# PRY417_Med.net
KiCad netlist of a schematic drawn in EAGLE
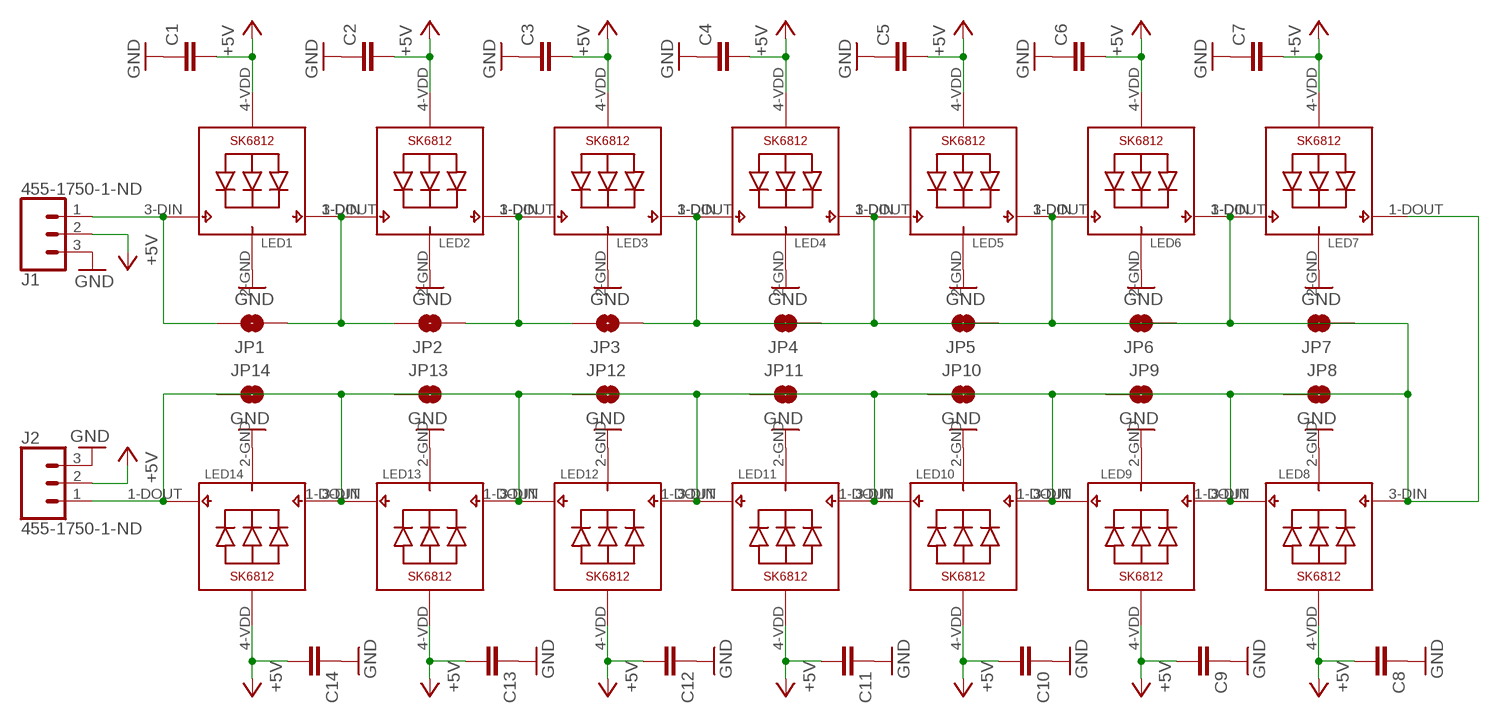
[diagram p0: schematic, sheet 1]

(export (version "E")
  (design (tool "Eeschema 10.0.6"))
  (components
    (comp (ref "C1")
      (value "C-EUC1206")
      (footprint "eagle-import:C1206")
      (libsource (lib "eagle-import") (part "C-EUC1206"))
    )
    (comp (ref "C2")
      (value "C-EUC1206")
      (footprint "eagle-import:C1206")
      (libsource (lib "eagle-import") (part "C-EUC1206"))
    )
    (comp (ref "C3")
      (value "C-EUC1206")
      (footprint "eagle-import:C1206")
      (libsource (lib "eagle-import") (part "C-EUC1206"))
    )
    (comp (ref "C4")
      (value "C-EUC1206")
      (footprint "eagle-import:C1206")
      (libsource (lib "eagle-import") (part "C-EUC1206"))
    )
    (comp (ref "C5")
      (value "C-EUC1206")
      (footprint "eagle-import:C1206")
      (libsource (lib "eagle-import") (part "C-EUC1206"))
    )
    (comp (ref "C6")
      (value "C-EUC1206")
      (footprint "eagle-import:C1206")
      (libsource (lib "eagle-import") (part "C-EUC1206"))
    )
    (comp (ref "C7")
      (value "C-EUC1206")
      (footprint "eagle-import:C1206")
      (libsource (lib "eagle-import") (part "C-EUC1206"))
    )
    (comp (ref "C8")
      (value "C-EUC1206")
      (footprint "eagle-import:C1206")
      (libsource (lib "eagle-import") (part "C-EUC1206"))
    )
    (comp (ref "C9")
      (value "C-EUC1206")
      (footprint "eagle-import:C1206")
      (libsource (lib "eagle-import") (part "C-EUC1206"))
    )
    (comp (ref "C10")
      (value "C-EUC1206")
      (footprint "eagle-import:C1206")
      (libsource (lib "eagle-import") (part "C-EUC1206"))
    )
    (comp (ref "C11")
      (value "C-EUC1206")
      (footprint "eagle-import:C1206")
      (libsource (lib "eagle-import") (part "C-EUC1206"))
    )
    (comp (ref "C12")
      (value "C-EUC1206")
      (footprint "eagle-import:C1206")
      (libsource (lib "eagle-import") (part "C-EUC1206"))
    )
    (comp (ref "C13")
      (value "C-EUC1206")
      (footprint "eagle-import:C1206")
      (libsource (lib "eagle-import") (part "C-EUC1206"))
    )
    (comp (ref "C14")
      (value "C-EUC1206")
      (footprint "eagle-import:C1206")
      (libsource (lib "eagle-import") (part "C-EUC1206"))
    )
    (comp (ref "J1")
      (value "455-1750-1-ND")
      (footprint "eagle-import:1X03")
      (libsource (lib "eagle-import") (part "CONN_03"))
    )
    (comp (ref "J2")
      (value "455-1750-1-ND")
      (footprint "eagle-import:1X03")
      (libsource (lib "eagle-import") (part "CONN_03"))
    )
    (comp (ref "JP1")
      (value "JUMPER-SMT_2_NO_SILK")
      (footprint "eagle-import:SMT-JUMPER_2_NO_SILK")
      (libsource (lib "eagle-import") (part "JUMPER-SMT_2_NO_SILK"))
    )
    (comp (ref "JP2")
      (value "JUMPER-SMT_2_NO_SILK")
      (footprint "eagle-import:SMT-JUMPER_2_NO_SILK")
      (libsource (lib "eagle-import") (part "JUMPER-SMT_2_NO_SILK"))
    )
    (comp (ref "JP3")
      (value "JUMPER-SMT_2_NO_SILK")
      (footprint "eagle-import:SMT-JUMPER_2_NO_SILK")
      (libsource (lib "eagle-import") (part "JUMPER-SMT_2_NO_SILK"))
    )
    (comp (ref "JP4")
      (value "JUMPER-SMT_2_NO_SILK")
      (footprint "eagle-import:SMT-JUMPER_2_NO_SILK")
      (libsource (lib "eagle-import") (part "JUMPER-SMT_2_NO_SILK"))
    )
    (comp (ref "JP5")
      (value "JUMPER-SMT_2_NO_SILK")
      (footprint "eagle-import:SMT-JUMPER_2_NO_SILK")
      (libsource (lib "eagle-import") (part "JUMPER-SMT_2_NO_SILK"))
    )
    (comp (ref "JP6")
      (value "JUMPER-SMT_2_NO_SILK")
      (footprint "eagle-import:SMT-JUMPER_2_NO_SILK")
      (libsource (lib "eagle-import") (part "JUMPER-SMT_2_NO_SILK"))
    )
    (comp (ref "JP7")
      (value "JUMPER-SMT_2_NO_SILK")
      (footprint "eagle-import:SMT-JUMPER_2_NO_SILK")
      (libsource (lib "eagle-import") (part "JUMPER-SMT_2_NO_SILK"))
    )
    (comp (ref "JP8")
      (value "JUMPER-SMT_2_NO_SILK")
      (footprint "eagle-import:SMT-JUMPER_2_NO_SILK")
      (libsource (lib "eagle-import") (part "JUMPER-SMT_2_NO_SILK"))
    )
    (comp (ref "JP9")
      (value "JUMPER-SMT_2_NO_SILK")
      (footprint "eagle-import:SMT-JUMPER_2_NO_SILK")
      (libsource (lib "eagle-import") (part "JUMPER-SMT_2_NO_SILK"))
    )
    (comp (ref "JP10")
      (value "JUMPER-SMT_2_NO_SILK")
      (footprint "eagle-import:SMT-JUMPER_2_NO_SILK")
      (libsource (lib "eagle-import") (part "JUMPER-SMT_2_NO_SILK"))
    )
    (comp (ref "JP11")
      (value "JUMPER-SMT_2_NO_SILK")
      (footprint "eagle-import:SMT-JUMPER_2_NO_SILK")
      (libsource (lib "eagle-import") (part "JUMPER-SMT_2_NO_SILK"))
    )
    (comp (ref "JP12")
      (value "JUMPER-SMT_2_NO_SILK")
      (footprint "eagle-import:SMT-JUMPER_2_NO_SILK")
      (libsource (lib "eagle-import") (part "JUMPER-SMT_2_NO_SILK"))
    )
    (comp (ref "JP13")
      (value "JUMPER-SMT_2_NO_SILK")
      (footprint "eagle-import:SMT-JUMPER_2_NO_SILK")
      (libsource (lib "eagle-import") (part "JUMPER-SMT_2_NO_SILK"))
    )
    (comp (ref "JP14")
      (value "JUMPER-SMT_2_NO_SILK")
      (footprint "eagle-import:SMT-JUMPER_2_NO_SILK")
      (libsource (lib "eagle-import") (part "JUMPER-SMT_2_NO_SILK"))
    )
    (comp (ref "LED1")
      (value "SK6812_3535")
      (footprint "eagle-import:LED3535")
      (libsource (lib "eagle-import") (part "SK6812_3535"))
    )
    (comp (ref "LED2")
      (value "SK6812_3535")
      (footprint "eagle-import:LED3535")
      (libsource (lib "eagle-import") (part "SK6812_3535"))
    )
    (comp (ref "LED3")
      (value "SK6812_3535")
      (footprint "eagle-import:LED3535")
      (libsource (lib "eagle-import") (part "SK6812_3535"))
    )
    (comp (ref "LED4")
      (value "SK6812_3535")
      (footprint "eagle-import:LED3535")
      (libsource (lib "eagle-import") (part "SK6812_3535"))
    )
    (comp (ref "LED5")
      (value "SK6812_3535")
      (footprint "eagle-import:LED3535")
      (libsource (lib "eagle-import") (part "SK6812_3535"))
    )
    (comp (ref "LED6")
      (value "SK6812_3535")
      (footprint "eagle-import:LED3535")
      (libsource (lib "eagle-import") (part "SK6812_3535"))
    )
    (comp (ref "LED7")
      (value "SK6812_3535")
      (footprint "eagle-import:LED3535")
      (libsource (lib "eagle-import") (part "SK6812_3535"))
    )
    (comp (ref "LED8")
      (value "SK6812_3535")
      (footprint "eagle-import:LED3535")
      (libsource (lib "eagle-import") (part "SK6812_3535"))
    )
    (comp (ref "LED9")
      (value "SK6812_3535")
      (footprint "eagle-import:LED3535")
      (libsource (lib "eagle-import") (part "SK6812_3535"))
    )
    (comp (ref "LED10")
      (value "SK6812_3535")
      (footprint "eagle-import:LED3535")
      (libsource (lib "eagle-import") (part "SK6812_3535"))
    )
    (comp (ref "LED11")
      (value "SK6812_3535")
      (footprint "eagle-import:LED3535")
      (libsource (lib "eagle-import") (part "SK6812_3535"))
    )
    (comp (ref "LED12")
      (value "SK6812_3535")
      (footprint "eagle-import:LED3535")
      (libsource (lib "eagle-import") (part "SK6812_3535"))
    )
    (comp (ref "LED13")
      (value "SK6812_3535")
      (footprint "eagle-import:LED3535")
      (libsource (lib "eagle-import") (part "SK6812_3535"))
    )
    (comp (ref "LED14")
      (value "SK6812_3535")
      (footprint "eagle-import:LED3535")
      (libsource (lib "eagle-import") (part "SK6812_3535"))
    )
  )
  (nets
    (net (code "1") (name "+5V") (class "Default")
      (node (ref "C1") (pin "2") (pinfunction "2_2") (pintype "passive"))
      (node (ref "C10") (pin "2") (pinfunction "2_2") (pintype "passive"))
      (node (ref "C11") (pin "2") (pinfunction "2_2") (pintype "passive"))
      (node (ref "C12") (pin "2") (pinfunction "2_2") (pintype "passive"))
      (node (ref "C13") (pin "2") (pinfunction "2_2") (pintype "passive"))
      (node (ref "C14") (pin "2") (pinfunction "2_2") (pintype "passive"))
      (node (ref "C2") (pin "2") (pinfunction "2_2") (pintype "passive"))
      (node (ref "C3") (pin "2") (pinfunction "2_2") (pintype "passive"))
      (node (ref "C4") (pin "2") (pinfunction "2_2") (pintype "passive"))
      (node (ref "C5") (pin "2") (pinfunction "2_2") (pintype "passive"))
      (node (ref "C6") (pin "2") (pinfunction "2_2") (pintype "passive"))
      (node (ref "C7") (pin "2") (pinfunction "2_2") (pintype "passive"))
      (node (ref "C8") (pin "2") (pinfunction "2_2") (pintype "passive"))
      (node (ref "C9") (pin "2") (pinfunction "2_2") (pintype "passive"))
      (node (ref "J1") (pin "2") (pinfunction "2_2") (pintype "passive"))
      (node (ref "J2") (pin "2") (pinfunction "2_2") (pintype "passive"))
      (node (ref "LED1") (pin "4-VDD") (pinfunction "VDD_4-VDD") (pintype "power_in"))
      (node (ref "LED10") (pin "4-VDD") (pinfunction "VDD_4-VDD") (pintype "power_in"))
      (node (ref "LED11") (pin "4-VDD") (pinfunction "VDD_4-VDD") (pintype "power_in"))
      (node (ref "LED12") (pin "4-VDD") (pinfunction "VDD_4-VDD") (pintype "power_in"))
      (node (ref "LED13") (pin "4-VDD") (pinfunction "VDD_4-VDD") (pintype "power_in"))
      (node (ref "LED14") (pin "4-VDD") (pinfunction "VDD_4-VDD") (pintype "power_in"))
      (node (ref "LED2") (pin "4-VDD") (pinfunction "VDD_4-VDD") (pintype "power_in"))
      (node (ref "LED3") (pin "4-VDD") (pinfunction "VDD_4-VDD") (pintype "power_in"))
      (node (ref "LED4") (pin "4-VDD") (pinfunction "VDD_4-VDD") (pintype "power_in"))
      (node (ref "LED5") (pin "4-VDD") (pinfunction "VDD_4-VDD") (pintype "power_in"))
      (node (ref "LED6") (pin "4-VDD") (pinfunction "VDD_4-VDD") (pintype "power_in"))
      (node (ref "LED7") (pin "4-VDD") (pinfunction "VDD_4-VDD") (pintype "power_in"))
      (node (ref "LED8") (pin "4-VDD") (pinfunction "VDD_4-VDD") (pintype "power_in"))
      (node (ref "LED9") (pin "4-VDD") (pinfunction "VDD_4-VDD") (pintype "power_in"))
    )
    (net (code "2") (name "GND") (class "Default")
      (node (ref "C1") (pin "1") (pinfunction "1_1") (pintype "passive"))
      (node (ref "C10") (pin "1") (pinfunction "1_1") (pintype "passive"))
      (node (ref "C11") (pin "1") (pinfunction "1_1") (pintype "passive"))
      (node (ref "C12") (pin "1") (pinfunction "1_1") (pintype "passive"))
      (node (ref "C13") (pin "1") (pinfunction "1_1") (pintype "passive"))
      (node (ref "C14") (pin "1") (pinfunction "1_1") (pintype "passive"))
      (node (ref "C2") (pin "1") (pinfunction "1_1") (pintype "passive"))
      (node (ref "C3") (pin "1") (pinfunction "1_1") (pintype "passive"))
      (node (ref "C4") (pin "1") (pinfunction "1_1") (pintype "passive"))
      (node (ref "C5") (pin "1") (pinfunction "1_1") (pintype "passive"))
      (node (ref "C6") (pin "1") (pinfunction "1_1") (pintype "passive"))
      (node (ref "C7") (pin "1") (pinfunction "1_1") (pintype "passive"))
      (node (ref "C8") (pin "1") (pinfunction "1_1") (pintype "passive"))
      (node (ref "C9") (pin "1") (pinfunction "1_1") (pintype "passive"))
      (node (ref "J1") (pin "3") (pinfunction "3_3") (pintype "passive"))
      (node (ref "J2") (pin "3") (pinfunction "3_3") (pintype "passive"))
      (node (ref "LED1") (pin "2-GND") (pinfunction "GND_2-GND") (pintype "power_in"))
      (node (ref "LED10") (pin "2-GND") (pinfunction "GND_2-GND") (pintype "power_in"))
      (node (ref "LED11") (pin "2-GND") (pinfunction "GND_2-GND") (pintype "power_in"))
      (node (ref "LED12") (pin "2-GND") (pinfunction "GND_2-GND") (pintype "power_in"))
      (node (ref "LED13") (pin "2-GND") (pinfunction "GND_2-GND") (pintype "power_in"))
      (node (ref "LED14") (pin "2-GND") (pinfunction "GND_2-GND") (pintype "power_in"))
      (node (ref "LED2") (pin "2-GND") (pinfunction "GND_2-GND") (pintype "power_in"))
      (node (ref "LED3") (pin "2-GND") (pinfunction "GND_2-GND") (pintype "power_in"))
      (node (ref "LED4") (pin "2-GND") (pinfunction "GND_2-GND") (pintype "power_in"))
      (node (ref "LED5") (pin "2-GND") (pinfunction "GND_2-GND") (pintype "power_in"))
      (node (ref "LED6") (pin "2-GND") (pinfunction "GND_2-GND") (pintype "power_in"))
      (node (ref "LED7") (pin "2-GND") (pinfunction "GND_2-GND") (pintype "power_in"))
      (node (ref "LED8") (pin "2-GND") (pinfunction "GND_2-GND") (pintype "power_in"))
      (node (ref "LED9") (pin "2-GND") (pinfunction "GND_2-GND") (pintype "power_in"))
    )
    (net (code "3") (name "Net-(LED1-DI)") (class "Default")
      (node (ref "J1") (pin "1") (pinfunction "1_1") (pintype "passive"))
      (node (ref "JP1") (pin "1") (pinfunction "1_1") (pintype "passive"))
      (node (ref "LED1") (pin "3-DIN") (pinfunction "DI_3-DIN") (pintype "input"))
    )
    (net (code "4") (name "Net-(LED1-DO)") (class "Default")
      (node (ref "JP1") (pin "2") (pinfunction "2_2") (pintype "passive"))
      (node (ref "JP2") (pin "1") (pinfunction "1_1") (pintype "passive"))
      (node (ref "LED1") (pin "1-DOUT") (pinfunction "DO_1-DOUT") (pintype "output"))
      (node (ref "LED2") (pin "3-DIN") (pinfunction "DI_3-DIN") (pintype "input"))
    )
    (net (code "5") (name "Net-(LED2-DO)") (class "Default")
      (node (ref "JP2") (pin "2") (pinfunction "2_2") (pintype "passive"))
      (node (ref "JP3") (pin "1") (pinfunction "1_1") (pintype "passive"))
      (node (ref "LED2") (pin "1-DOUT") (pinfunction "DO_1-DOUT") (pintype "output"))
      (node (ref "LED3") (pin "3-DIN") (pinfunction "DI_3-DIN") (pintype "input"))
    )
    (net (code "6") (name "Net-(LED3-DO)") (class "Default")
      (node (ref "JP3") (pin "2") (pinfunction "2_2") (pintype "passive"))
      (node (ref "JP4") (pin "2") (pinfunction "2_2") (pintype "passive"))
      (node (ref "LED3") (pin "1-DOUT") (pinfunction "DO_1-DOUT") (pintype "output"))
      (node (ref "LED4") (pin "3-DIN") (pinfunction "DI_3-DIN") (pintype "input"))
    )
    (net (code "7") (name "Net-(LED4-DO)") (class "Default")
      (node (ref "JP4") (pin "1") (pinfunction "1_1") (pintype "passive"))
      (node (ref "JP5") (pin "2") (pinfunction "2_2") (pintype "passive"))
      (node (ref "LED4") (pin "1-DOUT") (pinfunction "DO_1-DOUT") (pintype "output"))
      (node (ref "LED5") (pin "3-DIN") (pinfunction "DI_3-DIN") (pintype "input"))
    )
    (net (code "8") (name "Net-(LED5-DO)") (class "Default")
      (node (ref "JP5") (pin "1") (pinfunction "1_1") (pintype "passive"))
      (node (ref "JP6") (pin "2") (pinfunction "2_2") (pintype "passive"))
      (node (ref "LED5") (pin "1-DOUT") (pinfunction "DO_1-DOUT") (pintype "output"))
      (node (ref "LED6") (pin "3-DIN") (pinfunction "DI_3-DIN") (pintype "input"))
    )
    (net (code "9") (name "Net-(LED6-DO)") (class "Default")
      (node (ref "JP6") (pin "1") (pinfunction "1_1") (pintype "passive"))
      (node (ref "JP7") (pin "2") (pinfunction "2_2") (pintype "passive"))
      (node (ref "LED6") (pin "1-DOUT") (pinfunction "DO_1-DOUT") (pintype "output"))
      (node (ref "LED7") (pin "3-DIN") (pinfunction "DI_3-DIN") (pintype "input"))
    )
    (net (code "10") (name "Net-(LED7-DO)") (class "Default")
      (node (ref "JP7") (pin "1") (pinfunction "1_1") (pintype "passive"))
      (node (ref "JP8") (pin "2") (pinfunction "2_2") (pintype "passive"))
      (node (ref "LED7") (pin "1-DOUT") (pinfunction "DO_1-DOUT") (pintype "output"))
      (node (ref "LED8") (pin "3-DIN") (pinfunction "DI_3-DIN") (pintype "input"))
    )
    (net (code "11") (name "Net-(LED8-DO)") (class "Default")
      (node (ref "JP8") (pin "1") (pinfunction "1_1") (pintype "passive"))
      (node (ref "JP9") (pin "2") (pinfunction "2_2") (pintype "passive"))
      (node (ref "LED8") (pin "1-DOUT") (pinfunction "DO_1-DOUT") (pintype "output"))
      (node (ref "LED9") (pin "3-DIN") (pinfunction "DI_3-DIN") (pintype "input"))
    )
    (net (code "12") (name "Net-(LED10-DI)") (class "Default")
      (node (ref "JP10") (pin "2") (pinfunction "2_2") (pintype "passive"))
      (node (ref "JP9") (pin "1") (pinfunction "1_1") (pintype "passive"))
      (node (ref "LED10") (pin "3-DIN") (pinfunction "DI_3-DIN") (pintype "input"))
      (node (ref "LED9") (pin "1-DOUT") (pinfunction "DO_1-DOUT") (pintype "output"))
    )
    (net (code "13") (name "Net-(LED10-DO)") (class "Default")
      (node (ref "JP10") (pin "1") (pinfunction "1_1") (pintype "passive"))
      (node (ref "JP11") (pin "2") (pinfunction "2_2") (pintype "passive"))
      (node (ref "LED10") (pin "1-DOUT") (pinfunction "DO_1-DOUT") (pintype "output"))
      (node (ref "LED11") (pin "3-DIN") (pinfunction "DI_3-DIN") (pintype "input"))
    )
    (net (code "14") (name "Net-(LED11-DO)") (class "Default")
      (node (ref "JP11") (pin "1") (pinfunction "1_1") (pintype "passive"))
      (node (ref "JP12") (pin "2") (pinfunction "2_2") (pintype "passive"))
      (node (ref "LED11") (pin "1-DOUT") (pinfunction "DO_1-DOUT") (pintype "output"))
      (node (ref "LED12") (pin "3-DIN") (pinfunction "DI_3-DIN") (pintype "input"))
    )
    (net (code "15") (name "Net-(LED12-DO)") (class "Default")
      (node (ref "JP12") (pin "1") (pinfunction "1_1") (pintype "passive"))
      (node (ref "JP13") (pin "2") (pinfunction "2_2") (pintype "passive"))
      (node (ref "LED12") (pin "1-DOUT") (pinfunction "DO_1-DOUT") (pintype "output"))
      (node (ref "LED13") (pin "3-DIN") (pinfunction "DI_3-DIN") (pintype "input"))
    )
    (net (code "16") (name "Net-(LED13-DO)") (class "Default")
      (node (ref "JP13") (pin "1") (pinfunction "1_1") (pintype "passive"))
      (node (ref "JP14") (pin "2") (pinfunction "2_2") (pintype "passive"))
      (node (ref "LED13") (pin "1-DOUT") (pinfunction "DO_1-DOUT") (pintype "output"))
      (node (ref "LED14") (pin "3-DIN") (pinfunction "DI_3-DIN") (pintype "input"))
    )
    (net (code "17") (name "Net-(LED14-DO)") (class "Default")
      (node (ref "J2") (pin "1") (pinfunction "1_1") (pintype "passive"))
      (node (ref "JP14") (pin "1") (pinfunction "1_1") (pintype "passive"))
      (node (ref "LED14") (pin "1-DOUT") (pinfunction "DO_1-DOUT") (pintype "output"))
    )
  )
)
